# 140715_AriloTX_REV2_1_0_868MHZ_td.net
KiCad netlist of a schematic drawn in EAGLE
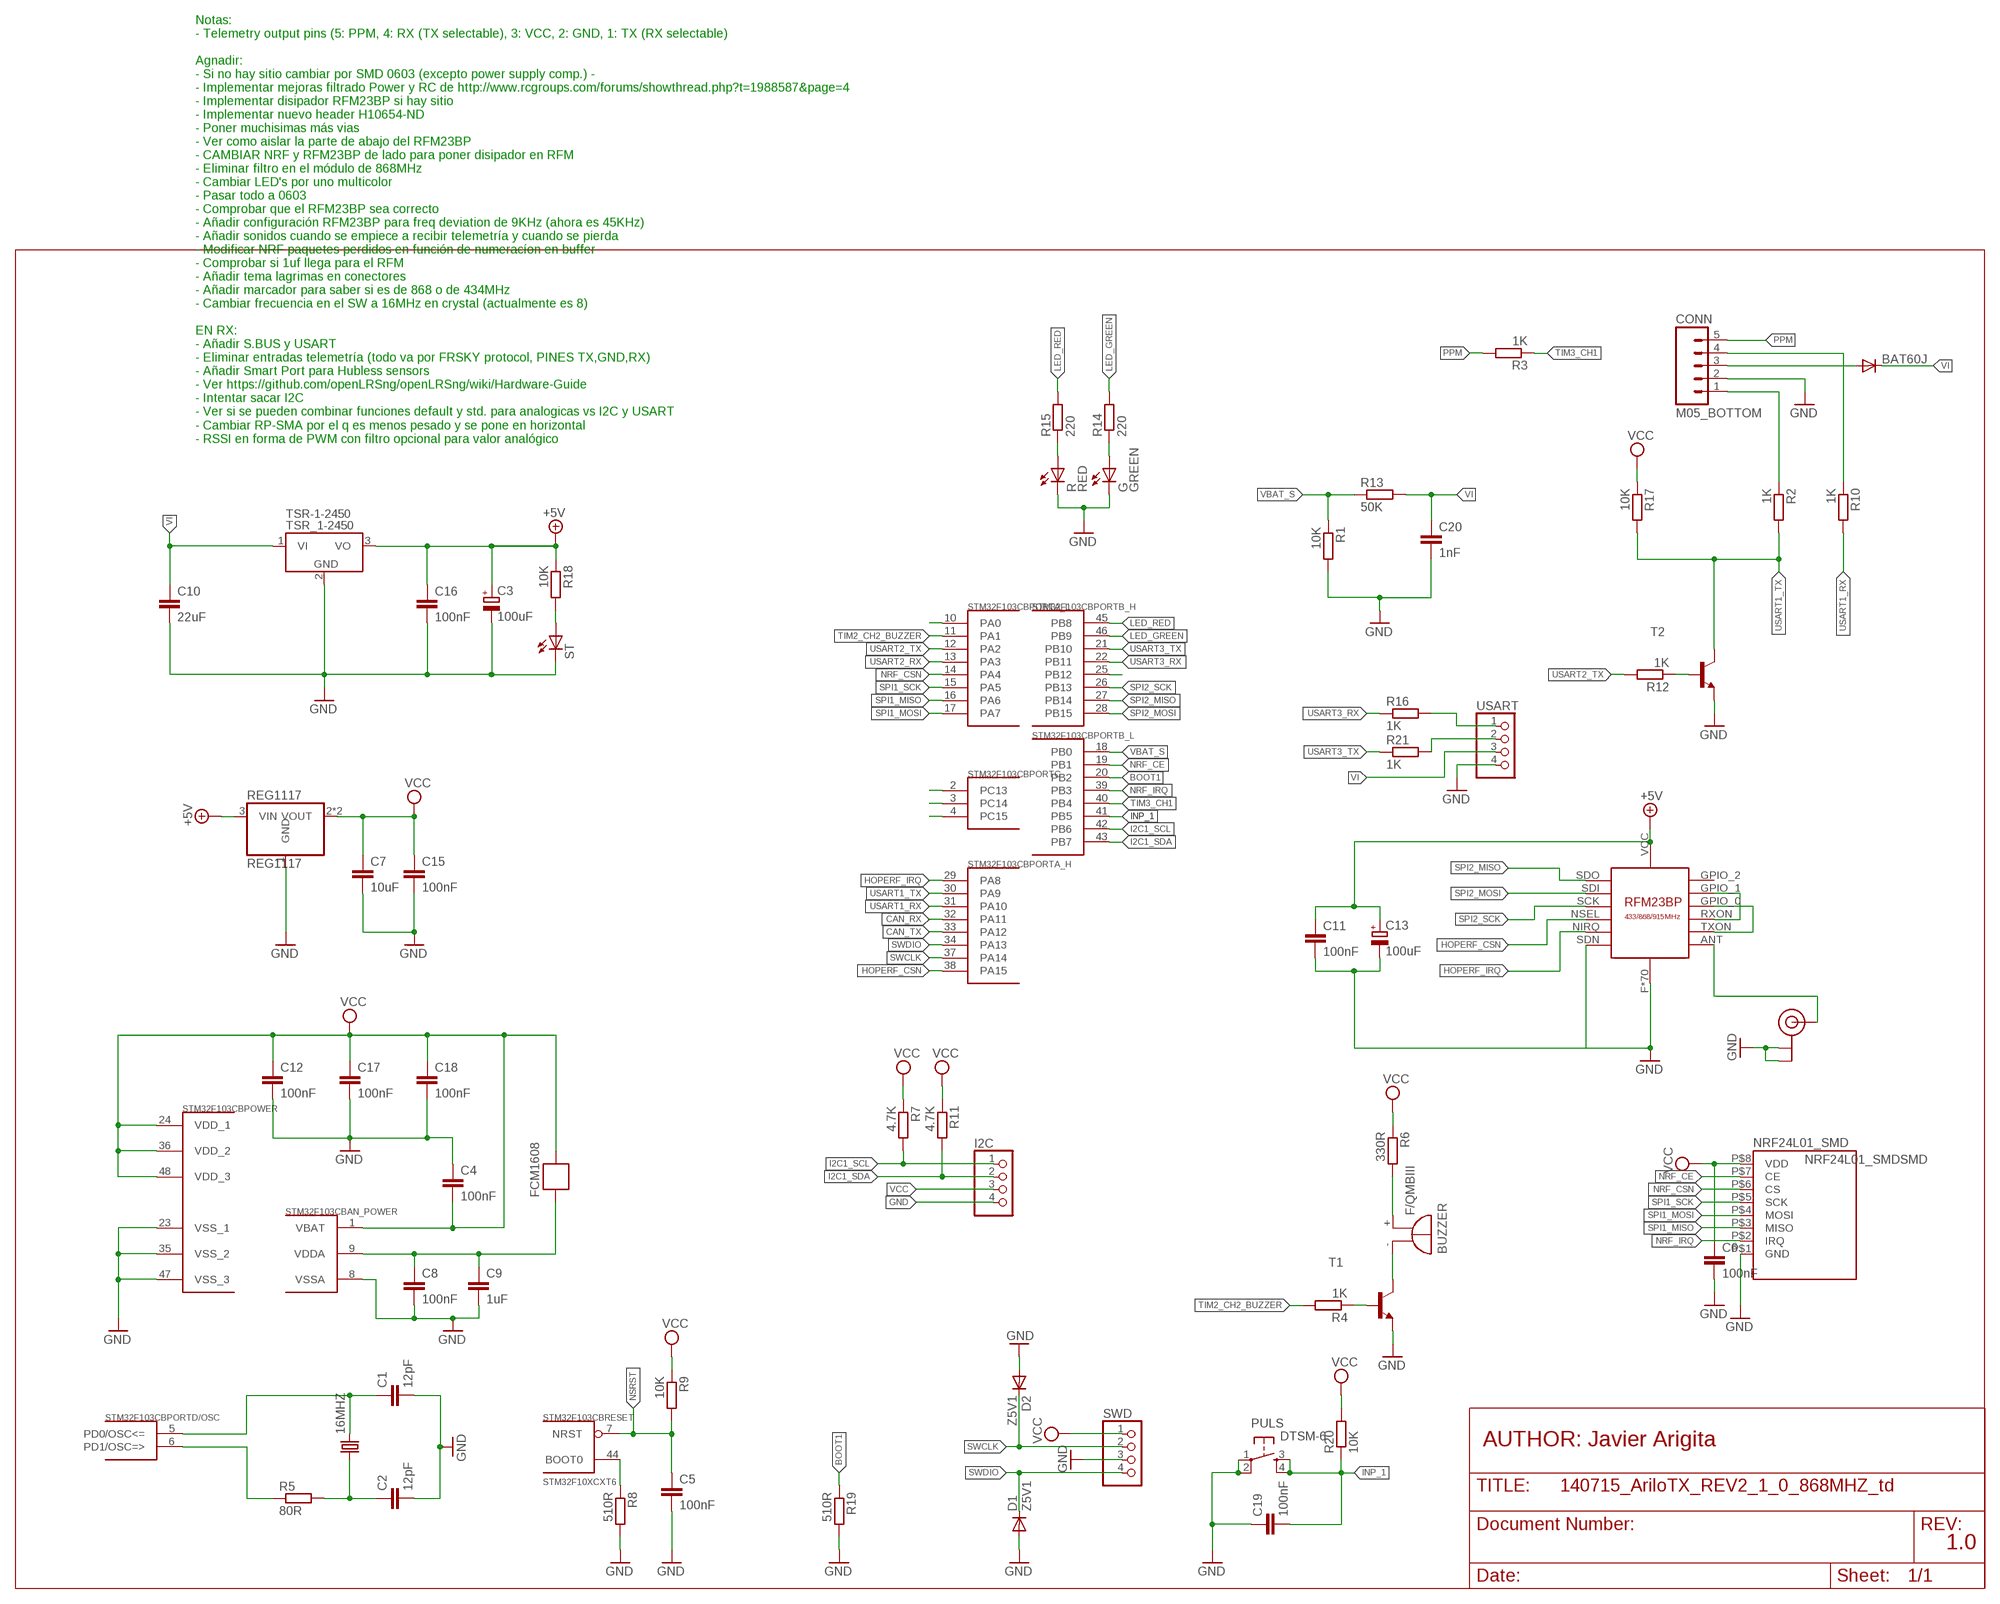
[diagram p0: schematic, sheet 1]

(export (version "E")
  (design (tool "Eeschema 10.0.6"))
  (components
    (comp (ref "16MHZ")
      (value "CRYSTAL5X3")
      (footprint "eagle-import:CRYSTAL-SMD-5X3")
      (libsource (lib "eagle-import") (part "CRYSTAL5X3"))
    )
    (comp (ref "BAT60J")
      (value "DIODE-SOD323-R")
      (footprint "eagle-import:SOD323-R")
      (libsource (lib "eagle-import") (part "DIODE-SOD323-R"))
    )
    (comp (ref "BUZZER")
      (value "F/QMBIII")
      (footprint "eagle-import:F_QMBIII")
      (libsource (lib "eagle-import") (part "F/QMBIII"))
    )
    (comp (ref "C1")
      (value "12pF")
      (footprint "eagle-import:C0603")
      (libsource (lib "eagle-import") (part "C-EUC0603"))
    )
    (comp (ref "C2")
      (value "12pF")
      (footprint "eagle-import:C0603")
      (libsource (lib "eagle-import") (part "C-EUC0603"))
    )
    (comp (ref "C3")
      (value "100uF")
      (footprint "eagle-import:SMC_B")
      (libsource (lib "eagle-import") (part "CPOL-EUSMCB"))
    )
    (comp (ref "C4")
      (value "100nF")
      (footprint "eagle-import:C0603")
      (libsource (lib "eagle-import") (part "C-EUC0603"))
    )
    (comp (ref "C5")
      (value "100nF")
      (footprint "eagle-import:C0603")
      (libsource (lib "eagle-import") (part "C-EUC0603"))
    )
    (comp (ref "C6")
      (value "100nF")
      (footprint "eagle-import:C0603")
      (libsource (lib "eagle-import") (part "C-EUC0603"))
    )
    (comp (ref "C7")
      (value "10uF")
      (footprint "eagle-import:C0805")
      (libsource (lib "eagle-import") (part "C-EUC0805"))
    )
    (comp (ref "C8")
      (value "100nF")
      (footprint "eagle-import:C0603")
      (libsource (lib "eagle-import") (part "C-EUC0603"))
    )
    (comp (ref "C9")
      (value "1uF")
      (footprint "eagle-import:C0603")
      (libsource (lib "eagle-import") (part "C-EUC0603"))
    )
    (comp (ref "C10")
      (value "22uF")
      (footprint "eagle-import:C3216")
      (libsource (lib "eagle-import") (part "resistor_C-EUC3216"))
    )
    (comp (ref "C11")
      (value "100nF")
      (footprint "eagle-import:C0603")
      (libsource (lib "eagle-import") (part "C-EUC0603"))
    )
    (comp (ref "C12")
      (value "100nF")
      (footprint "eagle-import:C0603")
      (libsource (lib "eagle-import") (part "C-EUC0603"))
    )
    (comp (ref "C13")
      (value "100uF")
      (footprint "eagle-import:SMC_B")
      (libsource (lib "eagle-import") (part "CPOL-EUSMCB"))
    )
    (comp (ref "C15")
      (value "100nF")
      (footprint "eagle-import:C0603")
      (libsource (lib "eagle-import") (part "C-EUC0603"))
    )
    (comp (ref "C16")
      (value "100nF")
      (footprint "eagle-import:C0603")
      (libsource (lib "eagle-import") (part "C-EUC0603"))
    )
    (comp (ref "C17")
      (value "100nF")
      (footprint "eagle-import:C0603")
      (libsource (lib "eagle-import") (part "C-EUC0603"))
    )
    (comp (ref "C18")
      (value "100nF")
      (footprint "eagle-import:C0603")
      (libsource (lib "eagle-import") (part "C-EUC0603"))
    )
    (comp (ref "C19")
      (value "100nF")
      (footprint "eagle-import:C0603")
      (libsource (lib "eagle-import") (part "C-EUC0603"))
    )
    (comp (ref "C20")
      (value "1nF")
      (footprint "eagle-import:C0603")
      (libsource (lib "eagle-import") (part "C-EUC0603"))
    )
    (comp (ref "CONN")
      (value "M05_BOTTOM")
      (footprint "eagle-import:M05_BOTTOM")
      (libsource (lib "eagle-import") (part "M05_BOTTOM"))
    )
    (comp (ref "D1")
      (value "Z5V1")
      (footprint "eagle-import:SOD323-R")
      (libsource (lib "eagle-import") (part "DIODE-SOD323-R"))
    )
    (comp (ref "D2")
      (value "Z5V1")
      (footprint "eagle-import:SOD323-R")
      (libsource (lib "eagle-import") (part "DIODE-SOD323-R"))
    )
    (comp (ref "FCM1608")
      (value "FERRITE-BEAD")
      (footprint "eagle-import:R0603")
      (libsource (lib "eagle-import") (part "FERRITE-BEAD"))
    )
    (comp (ref "G")
      (value "GREEN")
      (footprint "eagle-import:CHIP-LED0603")
      (libsource (lib "eagle-import") (part "LEDCHIP-LED0603"))
    )
    (comp (ref "I2C")
      (value "PINHD-1X4")
      (footprint "eagle-import:1X04")
      (libsource (lib "eagle-import") (part "PINHD-1X4"))
    )
    (comp (ref "NRF24L01_SMD")
      (value "NRF24L01_SMDSMD")
      (footprint "eagle-import:NRF24L01_SMD")
      (libsource (lib "eagle-import") (part "NRF24L01_SMDSMD"))
    )
    (comp (ref "PULS")
      (value "DTSM-6")
      (footprint "eagle-import:DTSM-6")
      (libsource (lib "eagle-import") (part "DTSM-6"))
    )
    (comp (ref "R")
      (value "RED")
      (footprint "eagle-import:CHIP-LED0603")
      (libsource (lib "eagle-import") (part "LEDCHIP-LED0603"))
    )
    (comp (ref "R1")
      (value "10K")
      (footprint "eagle-import:R0603")
      (libsource (lib "eagle-import") (part "R-EU_R0603"))
    )
    (comp (ref "R2")
      (value "1K")
      (footprint "eagle-import:R0603")
      (libsource (lib "eagle-import") (part "R-EU_R0603"))
    )
    (comp (ref "R3")
      (value "1K")
      (footprint "eagle-import:R0603")
      (libsource (lib "eagle-import") (part "R-EU_R0603"))
    )
    (comp (ref "R4")
      (value "1K")
      (footprint "eagle-import:R0603")
      (libsource (lib "eagle-import") (part "R-EU_R0603"))
    )
    (comp (ref "R5")
      (value "80R")
      (footprint "eagle-import:R0603")
      (libsource (lib "eagle-import") (part "R-EU_R0603"))
    )
    (comp (ref "R6")
      (value "330R")
      (footprint "eagle-import:R0603")
      (libsource (lib "eagle-import") (part "R-EU_R0603"))
    )
    (comp (ref "R7")
      (value "4.7K")
      (footprint "eagle-import:R0603")
      (libsource (lib "eagle-import") (part "R-EU_R0603"))
    )
    (comp (ref "R8")
      (value "510R")
      (footprint "eagle-import:R0603")
      (libsource (lib "eagle-import") (part "R-EU_R0603"))
    )
    (comp (ref "R9")
      (value "10K")
      (footprint "eagle-import:R0603")
      (libsource (lib "eagle-import") (part "R-EU_R0603"))
    )
    (comp (ref "R10")
      (value "1K")
      (footprint "eagle-import:R0603")
      (libsource (lib "eagle-import") (part "R-EU_R0603"))
    )
    (comp (ref "R11")
      (value "4.7K")
      (footprint "eagle-import:R0603")
      (libsource (lib "eagle-import") (part "R-EU_R0603"))
    )
    (comp (ref "R12")
      (value "1K")
      (footprint "eagle-import:R0603")
      (libsource (lib "eagle-import") (part "R-EU_R0603"))
    )
    (comp (ref "R13")
      (value "50K")
      (footprint "eagle-import:R0603")
      (libsource (lib "eagle-import") (part "R-EU_R0603"))
    )
    (comp (ref "R14")
      (value "220")
      (footprint "eagle-import:R0603")
      (libsource (lib "eagle-import") (part "R-EU_R0603"))
    )
    (comp (ref "R15")
      (value "220")
      (footprint "eagle-import:R0603")
      (libsource (lib "eagle-import") (part "R-EU_R0603"))
    )
    (comp (ref "R16")
      (value "1K")
      (footprint "eagle-import:R0603")
      (libsource (lib "eagle-import") (part "R-EU_R0603"))
    )
    (comp (ref "R17")
      (value "10K")
      (footprint "eagle-import:R0603")
      (libsource (lib "eagle-import") (part "R-EU_R0603"))
    )
    (comp (ref "R18")
      (value "10K")
      (footprint "eagle-import:R0603")
      (libsource (lib "eagle-import") (part "R-EU_R0603"))
    )
    (comp (ref "R19")
      (value "510R")
      (footprint "eagle-import:R0603")
      (libsource (lib "eagle-import") (part "R-EU_R0603"))
    )
    (comp (ref "R20")
      (value "10K")
      (footprint "eagle-import:R0603")
      (libsource (lib "eagle-import") (part "R-EU_R0603"))
    )
    (comp (ref "R21")
      (value "1K")
      (footprint "eagle-import:R0603")
      (libsource (lib "eagle-import") (part "R-EU_R0603"))
    )
    (comp (ref "REG1117")
      (value "REG1117")
      (footprint "eagle-import:SOT223")
      (libsource (lib "eagle-import") (part "REG1117"))
    )
    (comp (ref "ST")
      (value "LEDCHIP-LED0603")
      (footprint "eagle-import:CHIP-LED0603")
      (libsource (lib "eagle-import") (part "LEDCHIP-LED0603"))
    )
    (comp (ref "STM32F103CB")
      (value "STM32F10XCXT6")
      (footprint "eagle-import:TQFP48")
      (libsource (lib "eagle-import") (part "STM32F10XCXT6"))
    )
    (comp (ref "SWD")
      (value "PINHD-1X4")
      (footprint "eagle-import:1X04")
      (libsource (lib "eagle-import") (part "PINHD-1X4"))
    )
    (comp (ref "T1")
      (value "BC848-NPN-SOT23-BEC")
      (footprint "eagle-import:SOT23-BEC")
      (libsource (lib "eagle-import") (part "-NPN-SOT23-BECBC848"))
    )
    (comp (ref "T2")
      (value "BC848-NPN-SOT23-BEC")
      (footprint "eagle-import:SOT23-BEC")
      (libsource (lib "eagle-import") (part "-NPN-SOT23-BECBC848"))
    )
    (comp (ref "TSR-1-2450")
      (value "TSR_1-2450")
      (footprint "eagle-import:TSR-1")
      (libsource (lib "eagle-import") (part "TSR_1-2450"))
    )
    (comp (ref "U$1")
      (value "RFM23BP")
      (footprint "eagle-import:RFM23BP")
      (libsource (lib "eagle-import") (part "RFM23BP"))
    )
    (comp (ref "U.FL")
      (value "U.FL")
      (footprint "eagle-import:U.FL")
      (libsource (lib "eagle-import") (part "U.FL"))
    )
    (comp (ref "USART")
      (value "PINHD-1X4")
      (footprint "eagle-import:1X04")
      (libsource (lib "eagle-import") (part "PINHD-1X4"))
    )
  )
  (nets
    (net (code "1") (name "+5V") (class "Default")
      (node (ref "C11") (pin "1") (pinfunction "1_1") (pintype "passive"))
      (node (ref "C13") (pin "+") (pinfunction "+_+") (pintype "passive"))
      (node (ref "C16") (pin "1") (pinfunction "1_1") (pintype "passive"))
      (node (ref "C3") (pin "+") (pinfunction "+_+") (pintype "passive"))
      (node (ref "R18") (pin "1") (pinfunction "1_1") (pintype "passive"))
      (node (ref "REG1117") (pin "3") (pinfunction "VIN_3") (pintype "input"))
      (node (ref "TSR-1-2450") (pin "3") (pinfunction "VO_3") (pintype "power_in"))
      (node (ref "U$1") (pin "VCC") (pinfunction "VCC_VCC") (pintype "power_in"))
    )
    (net (code "2") (name "BOOT1") (class "Default")
      (node (ref "R19") (pin "1") (pinfunction "1_1") (pintype "passive"))
      (node (ref "STM32F103CB") (pin "20") (pinfunction "PB2_20") (pintype "bidirectional"))
    )
    (net (code "3") (name "CAN_RX") (class "Default")
      (node (ref "STM32F103CB") (pin "32") (pinfunction "PA11_32") (pintype "bidirectional"))
    )
    (net (code "4") (name "CAN_TX") (class "Default")
      (node (ref "STM32F103CB") (pin "33") (pinfunction "PA12_33") (pintype "bidirectional"))
    )
    (net (code "5") (name "GND") (class "Default")
      (node (ref "C1") (pin "2") (pinfunction "2_2") (pintype "passive"))
      (node (ref "C10") (pin "2") (pinfunction "2_2") (pintype "passive"))
      (node (ref "C11") (pin "2") (pinfunction "2_2") (pintype "passive"))
      (node (ref "C12") (pin "2") (pinfunction "2_2") (pintype "passive"))
      (node (ref "C13") (pin "-") (pinfunction "-_-") (pintype "passive"))
      (node (ref "C15") (pin "2") (pinfunction "2_2") (pintype "passive"))
      (node (ref "C16") (pin "2") (pinfunction "2_2") (pintype "passive"))
      (node (ref "C17") (pin "2") (pinfunction "2_2") (pintype "passive"))
      (node (ref "C18") (pin "2") (pinfunction "2_2") (pintype "passive"))
      (node (ref "C19") (pin "1") (pinfunction "1_1") (pintype "passive"))
      (node (ref "C2") (pin "2") (pinfunction "2_2") (pintype "passive"))
      (node (ref "C20") (pin "2") (pinfunction "2_2") (pintype "passive"))
      (node (ref "C3") (pin "-") (pinfunction "-_-") (pintype "passive"))
      (node (ref "C4") (pin "1") (pinfunction "1_1") (pintype "passive"))
      (node (ref "C5") (pin "2") (pinfunction "2_2") (pintype "passive"))
      (node (ref "C6") (pin "2") (pinfunction "2_2") (pintype "passive"))
      (node (ref "C7") (pin "2") (pinfunction "2_2") (pintype "passive"))
      (node (ref "C8") (pin "2") (pinfunction "2_2") (pintype "passive"))
      (node (ref "C9") (pin "2") (pinfunction "2_2") (pintype "passive"))
      (node (ref "CONN") (pin "2") (pinfunction "2_2") (pintype "passive"))
      (node (ref "D1") (pin "A") (pinfunction "A_A") (pintype "passive"))
      (node (ref "D2") (pin "A") (pinfunction "A_A") (pintype "passive"))
      (node (ref "G") (pin "C") (pinfunction "C_C") (pintype "passive"))
      (node (ref "I2C") (pin "4") (pinfunction "4_4") (pintype "passive"))
      (node (ref "NRF24L01_SMD") (pin "P$1") (pinfunction "GND_P$1") (pintype "power_in"))
      (node (ref "PULS") (pin "1") (pinfunction "1_1") (pintype "passive"))
      (node (ref "PULS") (pin "2") (pinfunction "2_2") (pintype "passive"))
      (node (ref "R") (pin "C") (pinfunction "C_C") (pintype "passive"))
      (node (ref "R1") (pin "2") (pinfunction "2_2") (pintype "passive"))
      (node (ref "R19") (pin "2") (pinfunction "2_2") (pintype "passive"))
      (node (ref "R8") (pin "2") (pinfunction "2_2") (pintype "passive"))
      (node (ref "REG1117") (pin "1") (pinfunction "GND_1") (pintype "power_in"))
      (node (ref "ST") (pin "C") (pinfunction "C_C") (pintype "passive"))
      (node (ref "STM32F103CB") (pin "23") (pinfunction "VSS_1_23") (pintype "power_in"))
      (node (ref "STM32F103CB") (pin "35") (pinfunction "VSS_2_35") (pintype "power_in"))
      (node (ref "STM32F103CB") (pin "47") (pinfunction "VSS_3_47") (pintype "power_in"))
      (node (ref "STM32F103CB") (pin "8") (pinfunction "VSSA_8") (pintype "power_in"))
      (node (ref "SWD") (pin "3") (pinfunction "3_3") (pintype "passive"))
      (node (ref "T1") (pin "E") (pinfunction "E_E") (pintype "passive"))
      (node (ref "T2") (pin "E") (pinfunction "E_E") (pintype "passive"))
      (node (ref "TSR-1-2450") (pin "2") (pinfunction "GND_2") (pintype "power_in"))
      (node (ref "U$1") (pin "F") (pinfunction "GND_F") (pintype "power_in"))
      (node (ref "U$1") (pin "F1") (pinfunction "GND_F1") (pintype "power_in"))
      (node (ref "U$1") (pin "F10") (pinfunction "GND_F10") (pintype "power_in"))
      (node (ref "U$1") (pin "F11") (pinfunction "GND_F11") (pintype "power_in"))
      (node (ref "U$1") (pin "F12") (pinfunction "GND_F12") (pintype "power_in"))
      (node (ref "U$1") (pin "F13") (pinfunction "GND_F13") (pintype "power_in"))
      (node (ref "U$1") (pin "F14") (pinfunction "GND_F14") (pintype "power_in"))
      (node (ref "U$1") (pin "F15") (pinfunction "GND_F15") (pintype "power_in"))
      (node (ref "U$1") (pin "F16") (pinfunction "GND_F16") (pintype "power_in"))
      (node (ref "U$1") (pin "F17") (pinfunction "GND_F17") (pintype "power_in"))
      (node (ref "U$1") (pin "F18") (pinfunction "GND_F18") (pintype "power_in"))
      (node (ref "U$1") (pin "F19") (pinfunction "GND_F19") (pintype "power_in"))
      (node (ref "U$1") (pin "F2") (pinfunction "GND_F2") (pintype "power_in"))
      (node (ref "U$1") (pin "F20") (pinfunction "GND_F20") (pintype "power_in"))
      (node (ref "U$1") (pin "F21") (pinfunction "GND_F21") (pintype "power_in"))
      (node (ref "U$1") (pin "F22") (pinfunction "GND_F22") (pintype "power_in"))
      (node (ref "U$1") (pin "F23") (pinfunction "GND_F23") (pintype "power_in"))
      (node (ref "U$1") (pin "F24") (pinfunction "GND_F24") (pintype "power_in"))
      (node (ref "U$1") (pin "F25") (pinfunction "GND_F25") (pintype "power_in"))
      (node (ref "U$1") (pin "F26") (pinfunction "GND_F26") (pintype "power_in"))
      (node (ref "U$1") (pin "F27") (pinfunction "GND_F27") (pintype "power_in"))
      (node (ref "U$1") (pin "F28") (pinfunction "GND_F28") (pintype "power_in"))
      (node (ref "U$1") (pin "F29") (pinfunction "GND_F29") (pintype "power_in"))
      (node (ref "U$1") (pin "F3") (pinfunction "GND_F3") (pintype "power_in"))
      (node (ref "U$1") (pin "F30") (pinfunction "GND_F30") (pintype "power_in"))
      (node (ref "U$1") (pin "F31") (pinfunction "GND_F31") (pintype "power_in"))
      (node (ref "U$1") (pin "F32") (pinfunction "GND_F32") (pintype "power_in"))
      (node (ref "U$1") (pin "F33") (pinfunction "GND_F33") (pintype "power_in"))
      (node (ref "U$1") (pin "F34") (pinfunction "GND_F34") (pintype "power_in"))
      (node (ref "U$1") (pin "F35") (pinfunction "GND_F35") (pintype "power_in"))
      (node (ref "U$1") (pin "F36") (pinfunction "GND_F36") (pintype "power_in"))
      (node (ref "U$1") (pin "F37") (pinfunction "GND_F37") (pintype "power_in"))
      (node (ref "U$1") (pin "F38") (pinfunction "GND_F38") (pintype "power_in"))
      (node (ref "U$1") (pin "F39") (pinfunction "GND_F39") (pintype "power_in"))
      (node (ref "U$1") (pin "F4") (pinfunction "GND_F4") (pintype "power_in"))
      (node (ref "U$1") (pin "F40") (pinfunction "GND_F40") (pintype "power_in"))
      (node (ref "U$1") (pin "F41") (pinfunction "GND_F41") (pintype "power_in"))
      (node (ref "U$1") (pin "F42") (pinfunction "GND_F42") (pintype "power_in"))
      (node (ref "U$1") (pin "F43") (pinfunction "GND_F43") (pintype "power_in"))
      (node (ref "U$1") (pin "F44") (pinfunction "GND_F44") (pintype "power_in"))
      (node (ref "U$1") (pin "F45") (pinfunction "GND_F45") (pintype "power_in"))
      (node (ref "U$1") (pin "F46") (pinfunction "GND_F46") (pintype "power_in"))
      (node (ref "U$1") (pin "F47") (pinfunction "GND_F47") (pintype "power_in"))
      (node (ref "U$1") (pin "F48") (pinfunction "GND_F48") (pintype "power_in"))
      (node (ref "U$1") (pin "F49") (pinfunction "GND_F49") (pintype "power_in"))
      (node (ref "U$1") (pin "F5") (pinfunction "GND_F5") (pintype "power_in"))
      (node (ref "U$1") (pin "F50") (pinfunction "GND_F50") (pintype "power_in"))
      (node (ref "U$1") (pin "F51") (pinfunction "GND_F51") (pintype "power_in"))
      (node (ref "U$1") (pin "F52") (pinfunction "GND_F52") (pintype "power_in"))
      (node (ref "U$1") (pin "F53") (pinfunction "GND_F53") (pintype "power_in"))
      (node (ref "U$1") (pin "F54") (pinfunction "GND_F54") (pintype "power_in"))
      (node (ref "U$1") (pin "F55") (pinfunction "GND_F55") (pintype "power_in"))
      (node (ref "U$1") (pin "F56") (pinfunction "GND_F56") (pintype "power_in"))
      (node (ref "U$1") (pin "F57") (pinfunction "GND_F57") (pintype "power_in"))
      (node (ref "U$1") (pin "F58") (pinfunction "GND_F58") (pintype "power_in"))
      (node (ref "U$1") (pin "F59") (pinfunction "GND_F59") (pintype "power_in"))
      (node (ref "U$1") (pin "F6") (pinfunction "GND_F6") (pintype "power_in"))
      (node (ref "U$1") (pin "F60") (pinfunction "GND_F60") (pintype "power_in"))
      (node (ref "U$1") (pin "F61") (pinfunction "GND_F61") (pintype "power_in"))
      (node (ref "U$1") (pin "F62") (pinfunction "GND_F62") (pintype "power_in"))
      (node (ref "U$1") (pin "F63") (pinfunction "GND_F63") (pintype "power_in"))
      (node (ref "U$1") (pin "F64") (pinfunction "GND_F64") (pintype "power_in"))
      (node (ref "U$1") (pin "F65") (pinfunction "GND_F65") (pintype "power_in"))
      (node (ref "U$1") (pin "F7") (pinfunction "GND_F7") (pintype "power_in"))
      (node (ref "U$1") (pin "F8") (pinfunction "GND_F8") (pintype "power_in"))
      (node (ref "U$1") (pin "F9") (pinfunction "GND_F9") (pintype "power_in"))
      (node (ref "U$1") (pin "GND1") (pinfunction "GND_GND1") (pintype "power_in"))
      (node (ref "U$1") (pin "GND2") (pinfunction "GND_GND2") (pintype "power_in"))
      (node (ref "U$1") (pin "GND3") (pinfunction "GND_GND3") (pintype "power_in"))
      (node (ref "U$1") (pin "GND_HEAT") (pinfunction "GND_GND_HEAT") (pintype "power_in"))
      (node (ref "U$1") (pin "SDN") (pinfunction "SDN_SDN") (pintype "bidirectional"))
      (node (ref "U.FL") (pin "P$1") (pinfunction "GND_P$1") (pintype "bidirectional"))
      (node (ref "U.FL") (pin "P$2") (pinfunction "GND_P$2") (pintype "bidirectional"))
      (node (ref "USART") (pin "4") (pinfunction "4_4") (pintype "passive"))
    )
    (net (code "6") (name "HOPERF_CSN") (class "Default")
      (node (ref "STM32F103CB") (pin "38") (pinfunction "PA15_38") (pintype "bidirectional"))
      (node (ref "U$1") (pin "NSEL") (pinfunction "NSEL_NSEL") (pintype "bidirectional"))
    )
    (net (code "7") (name "HOPERF_IRQ") (class "Default")
      (node (ref "STM32F103CB") (pin "29") (pinfunction "PA8_29") (pintype "bidirectional"))
      (node (ref "U$1") (pin "NIRQ") (pinfunction "NIRQ_NIRQ") (pintype "bidirectional"))
    )
    (net (code "8") (name "I2C1_SCL") (class "Default")
      (node (ref "I2C") (pin "1") (pinfunction "1_1") (pintype "passive"))
      (node (ref "R7") (pin "2") (pinfunction "2_2") (pintype "passive"))
      (node (ref "STM32F103CB") (pin "42") (pinfunction "PB6_42") (pintype "bidirectional"))
    )
    (net (code "9") (name "I2C1_SDA") (class "Default")
      (node (ref "I2C") (pin "2") (pinfunction "2_2") (pintype "passive"))
      (node (ref "R11") (pin "2") (pinfunction "2_2") (pintype "passive"))
      (node (ref "STM32F103CB") (pin "43") (pinfunction "PB7_43") (pintype "bidirectional"))
    )
    (net (code "10") (name "INP_1") (class "Default")
      (node (ref "C19") (pin "2") (pinfunction "2_2") (pintype "passive"))
      (node (ref "PULS") (pin "3") (pinfunction "3_3") (pintype "passive"))
      (node (ref "PULS") (pin "4") (pinfunction "4_4") (pintype "passive"))
      (node (ref "R20") (pin "1") (pinfunction "1_1") (pintype "passive"))
      (node (ref "STM32F103CB") (pin "41") (pinfunction "PB5_41") (pintype "bidirectional"))
    )
    (net (code "11") (name "LED_GREEN") (class "Default")
      (node (ref "R14") (pin "2") (pinfunction "2_2") (pintype "passive"))
      (node (ref "STM32F103CB") (pin "46") (pinfunction "PB9_46") (pintype "bidirectional"))
    )
    (net (code "12") (name "LED_RED") (class "Default")
      (node (ref "R15") (pin "2") (pinfunction "2_2") (pintype "passive"))
      (node (ref "STM32F103CB") (pin "45") (pinfunction "PB8_45") (pintype "bidirectional"))
    )
    (net (code "13") (name "NRF_CE") (class "Default")
      (node (ref "NRF24L01_SMD") (pin "P$7") (pinfunction "CE_P$7") (pintype "input"))
      (node (ref "STM32F103CB") (pin "19") (pinfunction "PB1_19") (pintype "bidirectional"))
    )
    (net (code "14") (name "NRF_CSN") (class "Default")
      (node (ref "NRF24L01_SMD") (pin "P$6") (pinfunction "CS_P$6") (pintype "input"))
      (node (ref "STM32F103CB") (pin "14") (pinfunction "PA4_14") (pintype "bidirectional"))
    )
    (net (code "15") (name "NRF_IRQ") (class "Default")
      (node (ref "NRF24L01_SMD") (pin "P$2") (pinfunction "IRQ_P$2") (pintype "output"))
      (node (ref "STM32F103CB") (pin "39") (pinfunction "PB3_39") (pintype "bidirectional"))
    )
    (net (code "16") (name "NSRST") (class "Default")
      (node (ref "C5") (pin "1") (pinfunction "1_1") (pintype "passive"))
      (node (ref "R9") (pin "2") (pinfunction "2_2") (pintype "passive"))
      (node (ref "STM32F103CB") (pin "7") (pinfunction "NRST_7") (pintype "input"))
    )
    (net (code "17") (name "Net-(16MHZ-2)") (class "Default")
      (node (ref "16MHZ") (pin "3") (pinfunction "2_3") (pintype "passive"))
      (node (ref "C1") (pin "1") (pinfunction "1_1") (pintype "passive"))
      (node (ref "STM32F103CB") (pin "5") (pinfunction "PD0/OSC<=_5") (pintype "bidirectional"))
    )
    (net (code "18") (name "Net-(16MHZ-Pad1)") (class "Default")
      (node (ref "16MHZ") (pin "1") (pinfunction "1_1") (pintype "passive"))
      (node (ref "C2") (pin "1") (pinfunction "1_1") (pintype "passive"))
      (node (ref "R5") (pin "2") (pinfunction "2_2") (pintype "passive"))
    )
    (net (code "19") (name "Net-(BAT60J-PadA)") (class "Default")
      (node (ref "BAT60J") (pin "A") (pinfunction "A_A") (pintype "passive"))
      (node (ref "CONN") (pin "3") (pinfunction "3_3") (pintype "passive"))
    )
    (net (code "20") (name "Net-(BUZZER-+)") (class "Default")
      (node (ref "BUZZER") (pin "-") (pinfunction "+_-") (pintype "passive"))
      (node (ref "T1") (pin "C") (pinfunction "C_C") (pintype "passive"))
    )
    (net (code "21") (name "Net-(BUZZER--)") (class "Default")
      (node (ref "BUZZER") (pin "+") (pinfunction "-_+") (pintype "passive"))
      (node (ref "R6") (pin "2") (pinfunction "2_2") (pintype "passive"))
    )
    (net (code "22") (name "Net-(CONN-Pad1)") (class "Default")
      (node (ref "CONN") (pin "1") (pinfunction "1_1") (pintype "passive"))
      (node (ref "R2") (pin "1") (pinfunction "1_1") (pintype "passive"))
    )
    (net (code "23") (name "Net-(CONN-Pad4)") (class "Default")
      (node (ref "CONN") (pin "4") (pinfunction "4_4") (pintype "passive"))
      (node (ref "R10") (pin "1") (pinfunction "1_1") (pintype "passive"))
    )
    (net (code "24") (name "Net-(FCM1608-P$2)") (class "Default")
      (node (ref "C8") (pin "1") (pinfunction "1_1") (pintype "passive"))
      (node (ref "C9") (pin "1") (pinfunction "1_1") (pintype "passive"))
      (node (ref "FCM1608") (pin "2") (pinfunction "P$2_2") (pintype "bidirectional"))
      (node (ref "STM32F103CB") (pin "9") (pinfunction "VDDA_9") (pintype "power_in"))
    )
    (net (code "25") (name "Net-(G-PadA)") (class "Default")
      (node (ref "G") (pin "A") (pinfunction "A_A") (pintype "passive"))
      (node (ref "R14") (pin "1") (pinfunction "1_1") (pintype "passive"))
    )
    (net (code "26") (name "Net-(R-PadA)") (class "Default")
      (node (ref "R") (pin "A") (pinfunction "A_A") (pintype "passive"))
      (node (ref "R15") (pin "1") (pinfunction "1_1") (pintype "passive"))
    )
    (net (code "27") (name "Net-(R4-Pad1)") (class "Default")
      (node (ref "R4") (pin "1") (pinfunction "1_1") (pintype "passive"))
      (node (ref "T1") (pin "B") (pinfunction "B_B") (pintype "passive"))
    )
    (net (code "28") (name "Net-(R12-Pad1)") (class "Default")
      (node (ref "R12") (pin "1") (pinfunction "1_1") (pintype "passive"))
      (node (ref "T2") (pin "B") (pinfunction "B_B") (pintype "passive"))
    )
    (net (code "29") (name "Net-(R16-Pad2)") (class "Default")
      (node (ref "R16") (pin "2") (pinfunction "2_2") (pintype "passive"))
      (node (ref "USART") (pin "1") (pinfunction "1_1") (pintype "passive"))
    )
    (net (code "30") (name "Net-(R18-Pad2)") (class "Default")
      (node (ref "R18") (pin "2") (pinfunction "2_2") (pintype "passive"))
      (node (ref "ST") (pin "A") (pinfunction "A_A") (pintype "passive"))
    )
    (net (code "31") (name "Net-(R21-Pad2)") (class "Default")
      (node (ref "R21") (pin "2") (pinfunction "2_2") (pintype "passive"))
      (node (ref "USART") (pin "2") (pinfunction "2_2") (pintype "passive"))
    )
    (net (code "32") (name "Net-(STM32F103CBG-PD1{slash}OSC=>)") (class "Default")
      (node (ref "R5") (pin "1") (pinfunction "1_1") (pintype "passive"))
      (node (ref "STM32F103CB") (pin "6") (pinfunction "PD1/OSC=>_6") (pintype "bidirectional"))
    )
    (net (code "33") (name "Net-(STM32F103CBI-BOOT0)") (class "Default")
      (node (ref "R8") (pin "1") (pinfunction "1_1") (pintype "passive"))
      (node (ref "STM32F103CB") (pin "44") (pinfunction "BOOT0_44") (pintype "input"))
    )
    (net (code "34") (name "Net-(U$1-PadGPIO_0)") (class "Default")
      (node (ref "U$1") (pin "GPIO_0") (pinfunction "GPIO_0_GPIO_0") (pintype "bidirectional"))
      (node (ref "U$1") (pin "TXON") (pinfunction "TXON_TXON") (pintype "bidirectional"))
    )
    (net (code "35") (name "Net-(U$1-PadGPIO_1)") (class "Default")
      (node (ref "U$1") (pin "GPIO_1") (pinfunction "GPIO_1_GPIO_1") (pintype "bidirectional"))
      (node (ref "U$1") (pin "RXON") (pinfunction "RXON_RXON") (pintype "bidirectional"))
    )
    (net (code "36") (name "Net-(U.FL-SIGNAL)") (class "Default")
      (node (ref "U$1") (pin "ANT") (pinfunction "ANT_ANT") (pintype "bidirectional"))
      (node (ref "U.FL") (pin "P$3") (pinfunction "SIGNAL_P$3") (pintype "bidirectional"))
    )
    (net (code "37") (name "PPM") (class "Default")
      (node (ref "CONN") (pin "5") (pinfunction "5_5") (pintype "passive"))
      (node (ref "R3") (pin "2") (pinfunction "2_2") (pintype "passive"))
    )
    (net (code "38") (name "SPI1_MISO") (class "Default")
      (node (ref "NRF24L01_SMD") (pin "P$3") (pinfunction "MISO_P$3") (pintype "output"))
      (node (ref "STM32F103CB") (pin "16") (pinfunction "PA6_16") (pintype "bidirectional"))
    )
    (net (code "39") (name "SPI1_MOSI") (class "Default")
      (node (ref "NRF24L01_SMD") (pin "P$4") (pinfunction "MOSI_P$4") (pintype "input"))
      (node (ref "STM32F103CB") (pin "17") (pinfunction "PA7_17") (pintype "bidirectional"))
    )
    (net (code "40") (name "SPI1_SCK") (class "Default")
      (node (ref "NRF24L01_SMD") (pin "P$5") (pinfunction "SCK_P$5") (pintype "input"))
      (node (ref "STM32F103CB") (pin "15") (pinfunction "PA5_15") (pintype "bidirectional"))
    )
    (net (code "41") (name "SPI2_MISO") (class "Default")
      (node (ref "STM32F103CB") (pin "27") (pinfunction "PB14_27") (pintype "bidirectional"))
      (node (ref "U$1") (pin "SDO") (pinfunction "SDO_SDO") (pintype "bidirectional"))
    )
    (net (code "42") (name "SPI2_MOSI") (class "Default")
      (node (ref "STM32F103CB") (pin "28") (pinfunction "PB15_28") (pintype "bidirectional"))
      (node (ref "U$1") (pin "SDI") (pinfunction "SDI_SDI") (pintype "bidirectional"))
    )
    (net (code "43") (name "SPI2_SCK") (class "Default")
      (node (ref "STM32F103CB") (pin "26") (pinfunction "PB13_26") (pintype "bidirectional"))
      (node (ref "U$1") (pin "SCK") (pinfunction "SCK_SCK") (pintype "bidirectional"))
    )
    (net (code "44") (name "SWCLK") (class "Default")
      (node (ref "D2") (pin "C") (pinfunction "C_C") (pintype "passive"))
      (node (ref "STM32F103CB") (pin "37") (pinfunction "PA14_37") (pintype "bidirectional"))
      (node (ref "SWD") (pin "2") (pinfunction "2_2") (pintype "passive"))
    )
    (net (code "45") (name "SWDIO") (class "Default")
      (node (ref "D1") (pin "C") (pinfunction "C_C") (pintype "passive"))
      (node (ref "STM32F103CB") (pin "34") (pinfunction "PA13_34") (pintype "bidirectional"))
      (node (ref "SWD") (pin "4") (pinfunction "4_4") (pintype "passive"))
    )
    (net (code "46") (name "TIM2_CH2_BUZZER") (class "Default")
      (node (ref "R4") (pin "2") (pinfunction "2_2") (pintype "passive"))
      (node (ref "STM32F103CB") (pin "11") (pinfunction "PA1_11") (pintype "bidirectional"))
    )
    (net (code "47") (name "TIM3_CH1") (class "Default")
      (node (ref "R3") (pin "1") (pinfunction "1_1") (pintype "passive"))
      (node (ref "STM32F103CB") (pin "40") (pinfunction "PB4_40") (pintype "bidirectional"))
    )
    (net (code "48") (name "USART1_RX") (class "Default")
      (node (ref "R10") (pin "2") (pinfunction "2_2") (pintype "passive"))
      (node (ref "STM32F103CB") (pin "31") (pinfunction "PA10_31") (pintype "bidirectional"))
    )
    (net (code "49") (name "USART1_TX") (class "Default")
      (node (ref "R17") (pin "2") (pinfunction "2_2") (pintype "passive"))
      (node (ref "R2") (pin "2") (pinfunction "2_2") (pintype "passive"))
      (node (ref "STM32F103CB") (pin "30") (pinfunction "PA9_30") (pintype "bidirectional"))
      (node (ref "T2") (pin "C") (pinfunction "C_C") (pintype "passive"))
    )
    (net (code "50") (name "USART2_RX") (class "Default")
      (node (ref "STM32F103CB") (pin "13") (pinfunction "PA3_13") (pintype "bidirectional"))
    )
    (net (code "51") (name "USART2_TX") (class "Default")
      (node (ref "R12") (pin "2") (pinfunction "2_2") (pintype "passive"))
      (node (ref "STM32F103CB") (pin "12") (pinfunction "PA2_12") (pintype "bidirectional"))
    )
    (net (code "52") (name "USART3_RX") (class "Default")
      (node (ref "R16") (pin "1") (pinfunction "1_1") (pintype "passive"))
      (node (ref "STM32F103CB") (pin "22") (pinfunction "PB11_22") (pintype "bidirectional"))
    )
    (net (code "53") (name "USART3_TX") (class "Default")
      (node (ref "R21") (pin "1") (pinfunction "1_1") (pintype "passive"))
      (node (ref "STM32F103CB") (pin "21") (pinfunction "PB10_21") (pintype "bidirectional"))
    )
    (net (code "54") (name "VBAT_S") (class "Default")
      (node (ref "R1") (pin "1") (pinfunction "1_1") (pintype "passive"))
      (node (ref "R13") (pin "1") (pinfunction "1_1") (pintype "passive"))
      (node (ref "STM32F103CB") (pin "18") (pinfunction "PB0_18") (pintype "bidirectional"))
    )
    (net (code "55") (name "VCC") (class "Default")
      (node (ref "C12") (pin "1") (pinfunction "1_1") (pintype "passive"))
      (node (ref "C15") (pin "1") (pinfunction "1_1") (pintype "passive"))
      (node (ref "C17") (pin "1") (pinfunction "1_1") (pintype "passive"))
      (node (ref "C18") (pin "1") (pinfunction "1_1") (pintype "passive"))
      (node (ref "C4") (pin "2") (pinfunction "2_2") (pintype "passive"))
      (node (ref "C6") (pin "1") (pinfunction "1_1") (pintype "passive"))
      (node (ref "C7") (pin "1") (pinfunction "1_1") (pintype "passive"))
      (node (ref "FCM1608") (pin "1") (pinfunction "P$1_1") (pintype "bidirectional"))
      (node (ref "I2C") (pin "3") (pinfunction "3_3") (pintype "passive"))
      (node (ref "NRF24L01_SMD") (pin "P$8") (pinfunction "VDD_P$8") (pintype "bidirectional"))
      (node (ref "R11") (pin "1") (pinfunction "1_1") (pintype "passive"))
      (node (ref "R17") (pin "1") (pinfunction "1_1") (pintype "passive"))
      (node (ref "R20") (pin "2") (pinfunction "2_2") (pintype "passive"))
      (node (ref "R6") (pin "1") (pinfunction "1_1") (pintype "passive"))
      (node (ref "R7") (pin "1") (pinfunction "1_1") (pintype "passive"))
      (node (ref "R9") (pin "1") (pinfunction "1_1") (pintype "passive"))
      (node (ref "REG1117") (pin "2") (pinfunction "VOUT_2") (pintype "power_in"))
      (node (ref "REG1117") (pin "4") (pinfunction "VOUT_4") (pintype "power_in"))
      (node (ref "STM32F103CB") (pin "1") (pinfunction "VBAT_1") (pintype "power_in"))
      (node (ref "STM32F103CB") (pin "24") (pinfunction "VDD_1_24") (pintype "power_in"))
      (node (ref "STM32F103CB") (pin "36") (pinfunction "VDD_2_36") (pintype "power_in"))
      (node (ref "STM32F103CB") (pin "48") (pinfunction "VDD_3_48") (pintype "power_in"))
      (node (ref "SWD") (pin "1") (pinfunction "1_1") (pintype "passive"))
    )
    (net (code "56") (name "VI") (class "Default")
      (node (ref "BAT60J") (pin "C") (pinfunction "C_C") (pintype "passive"))
      (node (ref "C10") (pin "1") (pinfunction "1_1") (pintype "passive"))
      (node (ref "C20") (pin "1") (pinfunction "1_1") (pintype "passive"))
      (node (ref "R13") (pin "2") (pinfunction "2_2") (pintype "passive"))
      (node (ref "TSR-1-2450") (pin "1") (pinfunction "VI_1") (pintype "power_in"))
      (node (ref "USART") (pin "3") (pinfunction "3_3") (pintype "passive"))
    )
    (net (code "57") (name "unconnected-(STM32F103CBC-PA0-Pad10)") (class "Default")
      (node (ref "STM32F103CB") (pin "10") (pinfunction "PA0_10") (pintype "bidirectional"))
    )
    (net (code "58") (name "unconnected-(STM32F103CBD-PB12-Pad25)") (class "Default")
      (node (ref "STM32F103CB") (pin "25") (pinfunction "PB12_25") (pintype "bidirectional"))
    )
    (net (code "59") (name "unconnected-(STM32F103CBF-PC13-Pad2)") (class "Default")
      (node (ref "STM32F103CB") (pin "2") (pinfunction "PC13_2") (pintype "bidirectional"))
    )
    (net (code "60") (name "unconnected-(STM32F103CBF-PC14-Pad3)") (class "Default")
      (node (ref "STM32F103CB") (pin "3") (pinfunction "PC14_3") (pintype "bidirectional"))
    )
    (net (code "61") (name "unconnected-(STM32F103CBF-PC15-Pad4)") (class "Default")
      (node (ref "STM32F103CB") (pin "4") (pinfunction "PC15_4") (pintype "bidirectional"))
    )
    (net (code "62") (name "unconnected-(U$1-PadGPIO_2)") (class "Default")
      (node (ref "U$1") (pin "GPIO_2") (pinfunction "GPIO_2_GPIO_2") (pintype "bidirectional"))
    )
  )
)
